# pic18f13k50.net
KiCad netlist of a schematic drawn in EAGLE
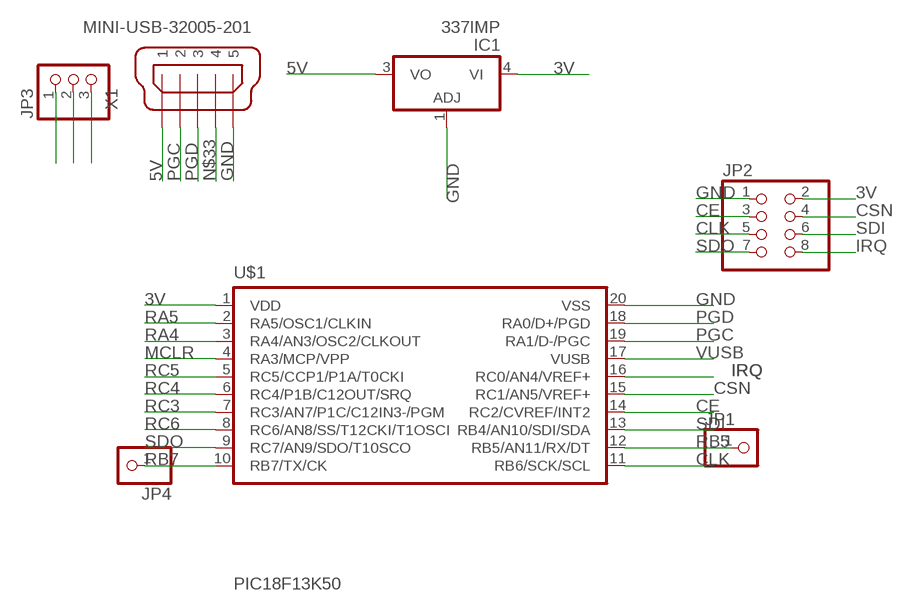
[diagram p0: schematic, sheet 1]

(export (version "E")
  (design (tool "Eeschema 10.0.6"))
  (components
    (comp (ref "IC1")
      (value "337IMP")
      (footprint "eagle-import:SOT223")
      (libsource (lib "eagle-import") (part "337IMP"))
    )
    (comp (ref "JP1")
      (value "PINHD-1X1")
      (footprint "eagle-import:1X01")
      (libsource (lib "eagle-import") (part "PINHD-1X1"))
    )
    (comp (ref "JP2")
      (value "PINHD-2X4")
      (footprint "eagle-import:2X04")
      (libsource (lib "eagle-import") (part "PINHD-2X4"))
    )
    (comp (ref "JP3")
      (value "PINHD-1X3")
      (footprint "eagle-import:1X03")
      (libsource (lib "eagle-import") (part "PINHD-1X3"))
    )
    (comp (ref "JP4")
      (value "PINHD-1X1")
      (footprint "eagle-import:1X01")
      (libsource (lib "eagle-import") (part "PINHD-1X1"))
    )
    (comp (ref "U$1")
      (value "PIC18F13K50")
      (footprint "eagle-import:SSOP20")
      (libsource (lib "eagle-import") (part "PIC18F13K50"))
    )
    (comp (ref "X1")
      (value "MINI-USB-32005-201")
      (footprint "eagle-import:32005-201")
      (libsource (lib "eagle-import") (part "MINI-USB-32005-201"))
    )
  )
  (nets
    (net (code "1") (name "/3V") (class "Default")
      (node (ref "IC1") (pin "4") (pinfunction "VI_4") (pintype "input"))
      (node (ref "JP2") (pin "2") (pinfunction "2_2") (pintype "passive"))
      (node (ref "JP3") (pin "2") (pinfunction "2_2") (pintype "passive"))
      (node (ref "U$1") (pin "1") (pinfunction "VDD_1") (pintype "power_in"))
    )
    (net (code "2") (name "/5V") (class "Default")
      (node (ref "IC1") (pin "3") (pinfunction "VO_3") (pintype "passive"))
      (node (ref "JP3") (pin "3") (pinfunction "3_3") (pintype "passive"))
      (node (ref "X1") (pin "1") (pinfunction "1_1") (pintype "passive"))
    )
    (net (code "3") (name "/CE") (class "Default")
      (node (ref "JP2") (pin "3") (pinfunction "3_3") (pintype "passive"))
      (node (ref "U$1") (pin "14") (pinfunction "RC2/CVREF/INT2_14") (pintype "bidirectional"))
    )
    (net (code "4") (name "/CLK") (class "Default")
      (node (ref "JP2") (pin "5") (pinfunction "5_5") (pintype "passive"))
      (node (ref "U$1") (pin "11") (pinfunction "RB6/SCK/SCL_11") (pintype "bidirectional"))
    )
    (net (code "5") (name "/CSN") (class "Default")
      (node (ref "JP2") (pin "4") (pinfunction "4_4") (pintype "passive"))
      (node (ref "U$1") (pin "15") (pinfunction "RC1/AN5/VREF+_15") (pintype "bidirectional"))
    )
    (net (code "6") (name "/GND") (class "Default")
      (node (ref "IC1") (pin "1") (pinfunction "ADJ_1") (pintype "input"))
      (node (ref "JP2") (pin "1") (pinfunction "1_1") (pintype "passive"))
      (node (ref "U$1") (pin "20") (pinfunction "VSS_20") (pintype "power_in"))
      (node (ref "X1") (pin "5") (pinfunction "5_5") (pintype "passive"))
    )
    (net (code "7") (name "/IRQ") (class "Default")
      (node (ref "JP2") (pin "8") (pinfunction "8_8") (pintype "passive"))
      (node (ref "U$1") (pin "16") (pinfunction "RC0/AN4/VREF+_16") (pintype "bidirectional"))
    )
    (net (code "8") (name "/MCLR") (class "Default")
      (node (ref "JP3") (pin "1") (pinfunction "1_1") (pintype "passive"))
      (node (ref "U$1") (pin "4") (pinfunction "RA3/MCP/VPP_4") (pintype "bidirectional"))
    )
    (net (code "9") (name "/N$33") (class "Default")
      (node (ref "X1") (pin "4") (pinfunction "4_4") (pintype "passive"))
    )
    (net (code "10") (name "/PGC") (class "Default")
      (node (ref "U$1") (pin "19") (pinfunction "RA1/D-/PGC_19") (pintype "bidirectional"))
      (node (ref "X1") (pin "2") (pinfunction "2_2") (pintype "passive"))
    )
    (net (code "11") (name "/PGD") (class "Default")
      (node (ref "U$1") (pin "18") (pinfunction "RA0/D+/PGD_18") (pintype "bidirectional"))
      (node (ref "X1") (pin "3") (pinfunction "3_3") (pintype "passive"))
    )
    (net (code "12") (name "/RA4") (class "Default")
      (node (ref "U$1") (pin "3") (pinfunction "RA4/AN3/OSC2/CLKOUT_3") (pintype "input"))
    )
    (net (code "13") (name "/RA5") (class "Default")
      (node (ref "U$1") (pin "2") (pinfunction "RA5/OSC1/CLKIN_2") (pintype "power_in"))
    )
    (net (code "14") (name "/RB5") (class "Default")
      (node (ref "JP1") (pin "1") (pinfunction "1_1") (pintype "passive"))
      (node (ref "U$1") (pin "12") (pinfunction "RB5/AN11/RX/DT_12") (pintype "bidirectional"))
    )
    (net (code "15") (name "/RB7") (class "Default")
      (node (ref "JP4") (pin "1") (pinfunction "1_1") (pintype "passive"))
      (node (ref "U$1") (pin "10") (pinfunction "RB7/TX/CK_10") (pintype "power_in"))
    )
    (net (code "16") (name "/RC3") (class "Default")
      (node (ref "U$1") (pin "7") (pinfunction "RC3/AN7/P1C/C12IN3-/PGM_7") (pintype "bidirectional"))
    )
    (net (code "17") (name "/RC4") (class "Default")
      (node (ref "U$1") (pin "6") (pinfunction "RC4/P1B/C12OUT/SRQ_6") (pintype "bidirectional"))
    )
    (net (code "18") (name "/RC5") (class "Default")
      (node (ref "U$1") (pin "5") (pinfunction "RC5/CCP1/P1A/T0CKI_5") (pintype "bidirectional"))
    )
    (net (code "19") (name "/RC6") (class "Default")
      (node (ref "U$1") (pin "8") (pinfunction "RC6/AN8/SS/T12CKI/T1OSCI_8") (pintype "bidirectional"))
    )
    (net (code "20") (name "/SDI") (class "Default")
      (node (ref "JP2") (pin "6") (pinfunction "6_6") (pintype "passive"))
      (node (ref "U$1") (pin "13") (pinfunction "RB4/AN10/SDI/SDA_13") (pintype "bidirectional"))
    )
    (net (code "21") (name "/SDO") (class "Default")
      (node (ref "JP2") (pin "7") (pinfunction "7_7") (pintype "passive"))
      (node (ref "U$1") (pin "9") (pinfunction "RC7/AN9/SDO/T10SCO_9") (pintype "bidirectional"))
    )
    (net (code "22") (name "/VUSB") (class "Default")
      (node (ref "U$1") (pin "17") (pinfunction "VUSB_17") (pintype "bidirectional"))
    )
  )
)
